# challenge0_5.net
KiCad netlist of a schematic drawn in EAGLE
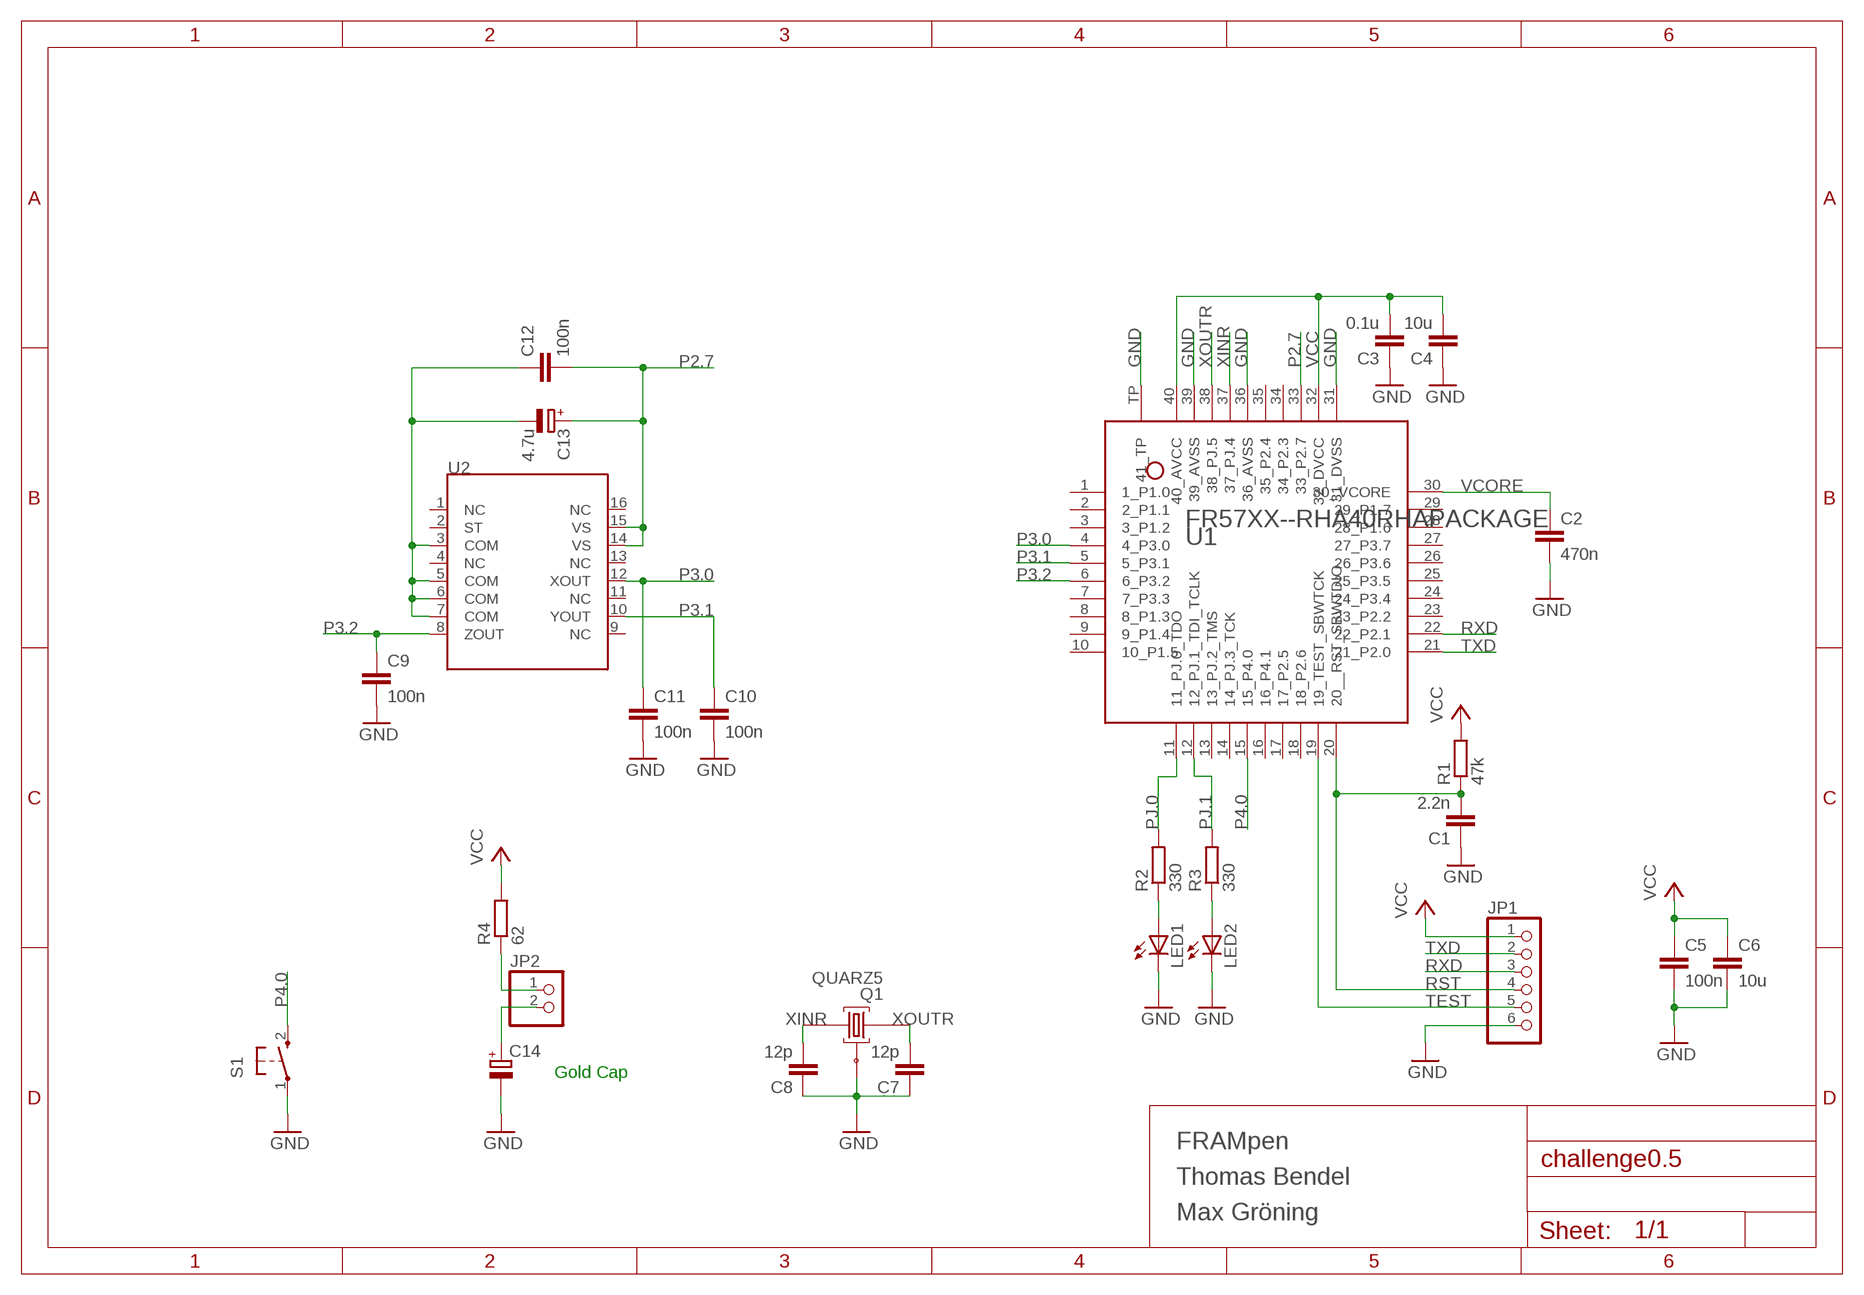
[diagram p0: schematic, sheet 1]

(export (version "E")
  (design (tool "Eeschema 10.0.6"))
  (components
    (comp (ref "C1")
      (value "2.2n")
      (footprint "eagle-import:C0805")
      (libsource (lib "eagle-import") (part "C-EUC0805"))
    )
    (comp (ref "C2")
      (value "470n")
      (footprint "eagle-import:C0805")
      (libsource (lib "eagle-import") (part "C-EUC0805"))
    )
    (comp (ref "C3")
      (value "0.1u")
      (footprint "eagle-import:C0805")
      (libsource (lib "eagle-import") (part "C-EUC0805"))
    )
    (comp (ref "C4")
      (value "10u")
      (footprint "eagle-import:C0805")
      (libsource (lib "eagle-import") (part "C-EUC0805"))
    )
    (comp (ref "C5")
      (value "100n")
      (footprint "eagle-import:C0805")
      (libsource (lib "eagle-import") (part "C-EUC0805"))
    )
    (comp (ref "C6")
      (value "10u")
      (footprint "eagle-import:C0805")
      (libsource (lib "eagle-import") (part "C-EUC0805"))
    )
    (comp (ref "C7")
      (value "12p")
      (footprint "eagle-import:C0805")
      (libsource (lib "eagle-import") (part "C-EUC0805"))
    )
    (comp (ref "C8")
      (value "12p")
      (footprint "eagle-import:C0805")
      (libsource (lib "eagle-import") (part "C-EUC0805"))
    )
    (comp (ref "C9")
      (value "100n")
      (footprint "eagle-import:C0805")
      (libsource (lib "eagle-import") (part "C-EUC0805"))
    )
    (comp (ref "C10")
      (value "100n")
      (footprint "eagle-import:C0805")
      (libsource (lib "eagle-import") (part "C-EUC0805"))
    )
    (comp (ref "C11")
      (value "100n")
      (footprint "eagle-import:C0805")
      (libsource (lib "eagle-import") (part "C-EUC0805"))
    )
    (comp (ref "C12")
      (value "100n")
      (footprint "eagle-import:C0805")
      (libsource (lib "eagle-import") (part "C-EUC0805"))
    )
    (comp (ref "C13")
      (value "4.7u")
      (footprint "eagle-import:SMC_A")
      (libsource (lib "eagle-import") (part "CPOL-EUSMCA"))
    )
    (comp (ref "C14")
      (value "CPOL-EUE10-20")
      (footprint "eagle-import:EB20D")
      (libsource (lib "eagle-import") (part "CPOL-EUE10-20"))
    )
    (comp (ref "JP1")
      (value "PINHD-1X6/90")
      (footprint "eagle-import:1X06_90")
      (libsource (lib "eagle-import") (part "PINHD-1X6/90"))
    )
    (comp (ref "JP2")
      (value "PINHD-1X2/90")
      (footprint "eagle-import:1X02_90")
      (libsource (lib "eagle-import") (part "PINHD-1X2/90"))
    )
    (comp (ref "LED1")
      (value "LEDCHIP-LED0805")
      (footprint "eagle-import:CHIP-LED0805")
      (libsource (lib "eagle-import") (part "LEDCHIP-LED0805"))
    )
    (comp (ref "LED2")
      (value "LEDCHIP-LED0805")
      (footprint "eagle-import:CHIP-LED0805")
      (libsource (lib "eagle-import") (part "LEDCHIP-LED0805"))
    )
    (comp (ref "Q1")
      (value "QUARZ5")
      (footprint "eagle-import:QUARZ5")
      (libsource (lib "eagle-import") (part "QUARZ5"))
    )
    (comp (ref "R1")
      (value "47k")
      (footprint "eagle-import:M0805")
      (libsource (lib "eagle-import") (part "R-EU_M0805"))
    )
    (comp (ref "R2")
      (value "330")
      (footprint "eagle-import:M0805")
      (libsource (lib "eagle-import") (part "R-EU_M0805"))
    )
    (comp (ref "R3")
      (value "330")
      (footprint "eagle-import:M0805")
      (libsource (lib "eagle-import") (part "R-EU_M0805"))
    )
    (comp (ref "R4")
      (value "62")
      (footprint "eagle-import:R1206")
      (libsource (lib "eagle-import") (part "R-EU_R1206"))
    )
    (comp (ref "S1")
      (value "PB")
      (footprint "eagle-import:PBTH")
      (libsource (lib "eagle-import") (part "PB"))
    )
    (comp (ref "U1")
      (value "FR57XX--RHA40RHAPACKAGE")
      (footprint "eagle-import:RHA40")
      (libsource (lib "eagle-import") (part "FR57XX--RHA40RHAPACKAGE"))
    )
    (comp (ref "U2")
      (value "ADXL330")
      (footprint "eagle-import:RSA16")
      (libsource (lib "eagle-import") (part "ADXL330"))
    )
  )
  (nets
    (net (code "1") (name "/P2.7") (class "Default")
      (node (ref "C12") (pin "2") (pinfunction "2_2") (pintype "passive"))
      (node (ref "C13") (pin "+") (pinfunction "+_+") (pintype "passive"))
      (node (ref "U1") (pin "33") (pinfunction "33_P2.7_33") (pintype "passive"))
      (node (ref "U2") (pin "14") (pinfunction "VS_14") (pintype "bidirectional"))
      (node (ref "U2") (pin "15") (pinfunction "VS_15") (pintype "bidirectional"))
    )
    (net (code "2") (name "/P3.0") (class "Default")
      (node (ref "C11") (pin "1") (pinfunction "1_1") (pintype "passive"))
      (node (ref "U1") (pin "4") (pinfunction "4_P3.0_4") (pintype "passive"))
      (node (ref "U2") (pin "12") (pinfunction "XOUT_12") (pintype "bidirectional"))
    )
    (net (code "3") (name "/P3.1") (class "Default")
      (node (ref "C10") (pin "1") (pinfunction "1_1") (pintype "passive"))
      (node (ref "U1") (pin "5") (pinfunction "5_P3.1_5") (pintype "passive"))
      (node (ref "U2") (pin "10") (pinfunction "YOUT_10") (pintype "bidirectional"))
    )
    (net (code "4") (name "/P3.2") (class "Default")
      (node (ref "C9") (pin "1") (pinfunction "1_1") (pintype "passive"))
      (node (ref "U1") (pin "6") (pinfunction "6_P3.2_6") (pintype "passive"))
      (node (ref "U2") (pin "8") (pinfunction "ZOUT_8") (pintype "bidirectional"))
    )
    (net (code "5") (name "/P4.0") (class "Default")
      (node (ref "S1") (pin "2") (pinfunction "S_2") (pintype "passive"))
      (node (ref "U1") (pin "15") (pinfunction "15_P4.0_15") (pintype "passive"))
    )
    (net (code "6") (name "/PJ.0") (class "Default")
      (node (ref "R2") (pin "2") (pinfunction "2_2") (pintype "passive"))
      (node (ref "U1") (pin "11") (pinfunction "11_PJ.0_TDO_11") (pintype "passive"))
    )
    (net (code "7") (name "/PJ.1") (class "Default")
      (node (ref "R3") (pin "2") (pinfunction "2_2") (pintype "passive"))
      (node (ref "U1") (pin "12") (pinfunction "12_PJ.1_TDI_TCLK_12") (pintype "passive"))
    )
    (net (code "8") (name "/RST") (class "Default")
      (node (ref "C1") (pin "2") (pinfunction "2_2") (pintype "passive"))
      (node (ref "JP1") (pin "4") (pinfunction "4_4") (pintype "passive"))
      (node (ref "R1") (pin "1") (pinfunction "1_1") (pintype "passive"))
      (node (ref "U1") (pin "20") (pinfunction "20__RST_SBWTDIO_20") (pintype "passive"))
    )
    (net (code "9") (name "/RXD") (class "Default")
      (node (ref "JP1") (pin "3") (pinfunction "3_3") (pintype "passive"))
      (node (ref "U1") (pin "22") (pinfunction "22_P2.1_22") (pintype "passive"))
    )
    (net (code "10") (name "/TEST") (class "Default")
      (node (ref "JP1") (pin "5") (pinfunction "5_5") (pintype "passive"))
      (node (ref "U1") (pin "19") (pinfunction "19_TEST_SBWTCK_19") (pintype "passive"))
    )
    (net (code "11") (name "/TXD") (class "Default")
      (node (ref "JP1") (pin "2") (pinfunction "2_2") (pintype "passive"))
      (node (ref "U1") (pin "21") (pinfunction "21_P2.0_21") (pintype "passive"))
    )
    (net (code "12") (name "/VCORE") (class "Default")
      (node (ref "C2") (pin "1") (pinfunction "1_1") (pintype "passive"))
      (node (ref "U1") (pin "30") (pinfunction "30_VCORE_30") (pintype "passive"))
    )
    (net (code "13") (name "/XINR") (class "Default")
      (node (ref "C8") (pin "2") (pinfunction "2_2") (pintype "passive"))
      (node (ref "Q1") (pin "1") (pinfunction "1_1") (pintype "passive"))
      (node (ref "U1") (pin "37") (pinfunction "37_PJ.4_37") (pintype "passive"))
    )
    (net (code "14") (name "/XOUTR") (class "Default")
      (node (ref "C7") (pin "2") (pinfunction "2_2") (pintype "passive"))
      (node (ref "Q1") (pin "2") (pinfunction "2_2") (pintype "passive"))
      (node (ref "U1") (pin "38") (pinfunction "38_PJ.5_38") (pintype "passive"))
    )
    (net (code "15") (name "GND") (class "Default")
      (node (ref "C1") (pin "1") (pinfunction "1_1") (pintype "passive"))
      (node (ref "C10") (pin "2") (pinfunction "2_2") (pintype "passive"))
      (node (ref "C11") (pin "2") (pinfunction "2_2") (pintype "passive"))
      (node (ref "C14") (pin "-") (pinfunction "-_-") (pintype "passive"))
      (node (ref "C2") (pin "2") (pinfunction "2_2") (pintype "passive"))
      (node (ref "C3") (pin "1") (pinfunction "1_1") (pintype "passive"))
      (node (ref "C4") (pin "1") (pinfunction "1_1") (pintype "passive"))
      (node (ref "C5") (pin "2") (pinfunction "2_2") (pintype "passive"))
      (node (ref "C6") (pin "2") (pinfunction "2_2") (pintype "passive"))
      (node (ref "C7") (pin "1") (pinfunction "1_1") (pintype "passive"))
      (node (ref "C8") (pin "1") (pinfunction "1_1") (pintype "passive"))
      (node (ref "C9") (pin "2") (pinfunction "2_2") (pintype "passive"))
      (node (ref "JP1") (pin "6") (pinfunction "6_6") (pintype "passive"))
      (node (ref "LED1") (pin "C") (pinfunction "C_C") (pintype "passive"))
      (node (ref "LED2") (pin "C") (pinfunction "C_C") (pintype "passive"))
      (node (ref "Q1") (pin "GND@0") (pinfunction "0_GND@0") (pintype "passive"))
      (node (ref "S1") (pin "1") (pinfunction "P_1") (pintype "passive"))
      (node (ref "U1") (pin "31") (pinfunction "31_DVSS_31") (pintype "passive"))
      (node (ref "U1") (pin "36") (pinfunction "36_AVSS_36") (pintype "passive"))
      (node (ref "U1") (pin "39") (pinfunction "39_AVSS_39") (pintype "passive"))
      (node (ref "U1") (pin "TP") (pinfunction "41_TP_TP") (pintype "passive"))
    )
    (net (code "16") (name "Net-(C12-Pad1)") (class "Default")
      (node (ref "C12") (pin "1") (pinfunction "1_1") (pintype "passive"))
      (node (ref "C13") (pin "-") (pinfunction "-_-") (pintype "passive"))
      (node (ref "U2") (pin "3") (pinfunction "COM_3") (pintype "bidirectional"))
      (node (ref "U2") (pin "5") (pinfunction "COM_5") (pintype "bidirectional"))
      (node (ref "U2") (pin "6") (pinfunction "COM_6") (pintype "bidirectional"))
      (node (ref "U2") (pin "7") (pinfunction "COM_7") (pintype "bidirectional"))
    )
    (net (code "17") (name "Net-(C14-Pad+)") (class "Default")
      (node (ref "C14") (pin "+") (pinfunction "+_+") (pintype "passive"))
      (node (ref "JP2") (pin "2") (pinfunction "2_2") (pintype "passive"))
    )
    (net (code "18") (name "Net-(JP2-Pad1)") (class "Default")
      (node (ref "JP2") (pin "1") (pinfunction "1_1") (pintype "passive"))
      (node (ref "R4") (pin "1") (pinfunction "1_1") (pintype "passive"))
    )
    (net (code "19") (name "Net-(LED1-PadA)") (class "Default")
      (node (ref "LED1") (pin "A") (pinfunction "A_A") (pintype "passive"))
      (node (ref "R2") (pin "1") (pinfunction "1_1") (pintype "passive"))
    )
    (net (code "20") (name "Net-(LED2-PadA)") (class "Default")
      (node (ref "LED2") (pin "A") (pinfunction "A_A") (pintype "passive"))
      (node (ref "R3") (pin "1") (pinfunction "1_1") (pintype "passive"))
    )
    (net (code "21") (name "VCC") (class "Default")
      (node (ref "C3") (pin "2") (pinfunction "2_2") (pintype "passive"))
      (node (ref "C4") (pin "2") (pinfunction "2_2") (pintype "passive"))
      (node (ref "C5") (pin "1") (pinfunction "1_1") (pintype "passive"))
      (node (ref "C6") (pin "1") (pinfunction "1_1") (pintype "passive"))
      (node (ref "JP1") (pin "1") (pinfunction "1_1") (pintype "passive"))
      (node (ref "R1") (pin "2") (pinfunction "2_2") (pintype "passive"))
      (node (ref "R4") (pin "2") (pinfunction "2_2") (pintype "passive"))
      (node (ref "U1") (pin "32") (pinfunction "32_DVCC_32") (pintype "passive"))
      (node (ref "U1") (pin "40") (pinfunction "40_AVCC_40") (pintype "passive"))
    )
    (net (code "22") (name "unconnected-(U1-1_P1.0-Pad1)") (class "Default")
      (node (ref "U1") (pin "1") (pinfunction "1_P1.0_1") (pintype "passive"))
    )
    (net (code "23") (name "unconnected-(U1-2_P1.1-Pad2)") (class "Default")
      (node (ref "U1") (pin "2") (pinfunction "2_P1.1_2") (pintype "passive"))
    )
    (net (code "24") (name "unconnected-(U1-3_P1.2-Pad3)") (class "Default")
      (node (ref "U1") (pin "3") (pinfunction "3_P1.2_3") (pintype "passive"))
    )
    (net (code "25") (name "unconnected-(U1-7_P3.3-Pad7)") (class "Default")
      (node (ref "U1") (pin "7") (pinfunction "7_P3.3_7") (pintype "passive"))
    )
    (net (code "26") (name "unconnected-(U1-8_P1.3-Pad8)") (class "Default")
      (node (ref "U1") (pin "8") (pinfunction "8_P1.3_8") (pintype "passive"))
    )
    (net (code "27") (name "unconnected-(U1-9_P1.4-Pad9)") (class "Default")
      (node (ref "U1") (pin "9") (pinfunction "9_P1.4_9") (pintype "passive"))
    )
    (net (code "28") (name "unconnected-(U1-10_P1.5-Pad10)") (class "Default")
      (node (ref "U1") (pin "10") (pinfunction "10_P1.5_10") (pintype "passive"))
    )
    (net (code "29") (name "unconnected-(U1-13_PJ.2_TMS-Pad13)") (class "Default")
      (node (ref "U1") (pin "13") (pinfunction "13_PJ.2_TMS_13") (pintype "passive"))
    )
    (net (code "30") (name "unconnected-(U1-14_PJ.3_TCK-Pad14)") (class "Default")
      (node (ref "U1") (pin "14") (pinfunction "14_PJ.3_TCK_14") (pintype "passive"))
    )
    (net (code "31") (name "unconnected-(U1-16_P4.1-Pad16)") (class "Default")
      (node (ref "U1") (pin "16") (pinfunction "16_P4.1_16") (pintype "passive"))
    )
    (net (code "32") (name "unconnected-(U1-17_P2.5-Pad17)") (class "Default")
      (node (ref "U1") (pin "17") (pinfunction "17_P2.5_17") (pintype "passive"))
    )
    (net (code "33") (name "unconnected-(U1-18_P2.6-Pad18)") (class "Default")
      (node (ref "U1") (pin "18") (pinfunction "18_P2.6_18") (pintype "passive"))
    )
    (net (code "34") (name "unconnected-(U1-23_P2.2-Pad23)") (class "Default")
      (node (ref "U1") (pin "23") (pinfunction "23_P2.2_23") (pintype "passive"))
    )
    (net (code "35") (name "unconnected-(U1-24_P3.4-Pad24)") (class "Default")
      (node (ref "U1") (pin "24") (pinfunction "24_P3.4_24") (pintype "passive"))
    )
    (net (code "36") (name "unconnected-(U1-25_P3.5-Pad25)") (class "Default")
      (node (ref "U1") (pin "25") (pinfunction "25_P3.5_25") (pintype "passive"))
    )
    (net (code "37") (name "unconnected-(U1-26_P3.6-Pad26)") (class "Default")
      (node (ref "U1") (pin "26") (pinfunction "26_P3.6_26") (pintype "passive"))
    )
    (net (code "38") (name "unconnected-(U1-27_P3.7-Pad27)") (class "Default")
      (node (ref "U1") (pin "27") (pinfunction "27_P3.7_27") (pintype "passive"))
    )
    (net (code "39") (name "unconnected-(U1-28_P1.6-Pad28)") (class "Default")
      (node (ref "U1") (pin "28") (pinfunction "28_P1.6_28") (pintype "passive"))
    )
    (net (code "40") (name "unconnected-(U1-29_P1.7-Pad29)") (class "Default")
      (node (ref "U1") (pin "29") (pinfunction "29_P1.7_29") (pintype "passive"))
    )
    (net (code "41") (name "unconnected-(U1-34_P2.3-Pad34)") (class "Default")
      (node (ref "U1") (pin "34") (pinfunction "34_P2.3_34") (pintype "passive"))
    )
    (net (code "42") (name "unconnected-(U1-35_P2.4-Pad35)") (class "Default")
      (node (ref "U1") (pin "35") (pinfunction "35_P2.4_35") (pintype "passive"))
    )
    (net (code "43") (name "unconnected-(U2-NC-Pad1)") (class "Default")
      (node (ref "U2") (pin "1") (pinfunction "NC_1") (pintype "bidirectional"))
    )
    (net (code "44") (name "unconnected-(U2-NC-Pad4)") (class "Default")
      (node (ref "U2") (pin "4") (pinfunction "NC_4") (pintype "bidirectional"))
    )
    (net (code "45") (name "unconnected-(U2-NC-Pad9)") (class "Default")
      (node (ref "U2") (pin "9") (pinfunction "NC_9") (pintype "bidirectional"))
    )
    (net (code "46") (name "unconnected-(U2-NC-Pad11)") (class "Default")
      (node (ref "U2") (pin "11") (pinfunction "NC_11") (pintype "bidirectional"))
    )
    (net (code "47") (name "unconnected-(U2-NC-Pad13)") (class "Default")
      (node (ref "U2") (pin "13") (pinfunction "NC_13") (pintype "bidirectional"))
    )
    (net (code "48") (name "unconnected-(U2-NC-Pad16)") (class "Default")
      (node (ref "U2") (pin "16") (pinfunction "NC_16") (pintype "bidirectional"))
    )
    (net (code "49") (name "unconnected-(U2-ST-Pad2)") (class "Default")
      (node (ref "U2") (pin "2") (pinfunction "ST_2") (pintype "bidirectional"))
    )
  )
)
